# ATtiny85_Programmer.net
KiCad netlist of a schematic drawn in EAGLE
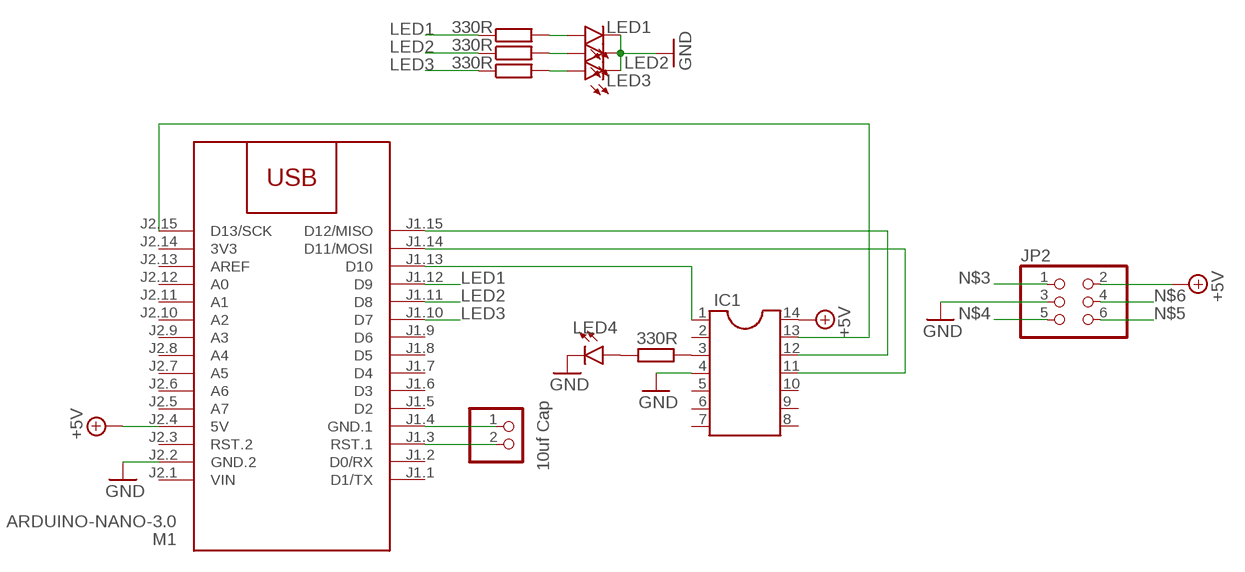
[diagram p0: schematic, sheet 1]

(export (version "E")
  (design (tool "Eeschema 10.0.6"))
  (components
    (comp (ref "IC1")
      (value "DIL14")
      (footprint "eagle-import:DIL14")
      (libsource (lib "eagle-import") (part "DIL14"))
    )
    (comp (ref "JP1")
      (value "10uf Cap")
      (footprint "eagle-import:1X02")
      (libsource (lib "eagle-import") (part "PINHD-1X2"))
    )
    (comp (ref "JP2")
      (value "PINHD-2X3")
      (footprint "eagle-import:2X03")
      (libsource (lib "eagle-import") (part "PINHD-2X3"))
    )
    (comp (ref "LED1")
      (value "LED3MM")
      (footprint "eagle-import:LED3MM")
      (libsource (lib "eagle-import") (part "LED3MM"))
    )
    (comp (ref "LED2")
      (value "LED3MM")
      (footprint "eagle-import:LED3MM")
      (libsource (lib "eagle-import") (part "LED3MM"))
    )
    (comp (ref "LED3")
      (value "LED3MM")
      (footprint "eagle-import:LED3MM")
      (libsource (lib "eagle-import") (part "LED3MM"))
    )
    (comp (ref "LED4")
      (value "LED3MM")
      (footprint "eagle-import:LED3MM")
      (libsource (lib "eagle-import") (part "LED3MM"))
    )
    (comp (ref "M1")
      (value "ARDUINO-NANO-3.0")
      (footprint "eagle-import:ARDUINO-NANO-3.0")
      (libsource (lib "eagle-import") (part "ARDUINO-NANO-3.0"))
    )
    (comp (ref "R1")
      (value "330R")
      (footprint "eagle-import:0207_10")
      (libsource (lib "eagle-import") (part "R-EU_0207/10"))
    )
    (comp (ref "R2")
      (value "330R")
      (footprint "eagle-import:0207_10")
      (libsource (lib "eagle-import") (part "R-EU_0207/10"))
    )
    (comp (ref "R3")
      (value "330R")
      (footprint "eagle-import:0207_10")
      (libsource (lib "eagle-import") (part "R-EU_0207/10"))
    )
    (comp (ref "R4")
      (value "330R")
      (footprint "eagle-import:0207_10")
      (libsource (lib "eagle-import") (part "R-EU_0207/10"))
    )
  )
  (nets
    (net (code "1") (name "+5V") (class "Default")
      (node (ref "IC1") (pin "14") (pinfunction "14_14") (pintype "passive"))
      (node (ref "JP2") (pin "2") (pinfunction "2_2") (pintype "passive"))
      (node (ref "M1") (pin "J2.4") (pinfunction "5V_J2.4") (pintype "power_in"))
    )
    (net (code "2") (name "/3V3") (class "Default")
      (node (ref "M1") (pin "J2.14") (pinfunction "3V3_J2.14") (pintype "power_in"))
    )
    (net (code "3") (name "/LED1") (class "Default")
      (node (ref "M1") (pin "J1.12") (pinfunction "D9_J1.12") (pintype "bidirectional"))
      (node (ref "R4") (pin "1") (pinfunction "1_1") (pintype "passive"))
    )
    (net (code "4") (name "/LED2") (class "Default")
      (node (ref "M1") (pin "J1.11") (pinfunction "D8_J1.11") (pintype "bidirectional"))
      (node (ref "R1") (pin "1") (pinfunction "1_1") (pintype "passive"))
    )
    (net (code "5") (name "/LED3") (class "Default")
      (node (ref "M1") (pin "J1.10") (pinfunction "D7_J1.10") (pintype "bidirectional"))
      (node (ref "R2") (pin "1") (pinfunction "1_1") (pintype "passive"))
    )
    (net (code "6") (name "/N$3") (class "Default")
      (node (ref "IC1") (pin "1") (pinfunction "1_1") (pintype "passive"))
      (node (ref "JP2") (pin "1") (pinfunction "1_1") (pintype "passive"))
      (node (ref "M1") (pin "J1.13") (pinfunction "D10_J1.13") (pintype "bidirectional"))
    )
    (net (code "7") (name "/N$4") (class "Default")
      (node (ref "IC1") (pin "11") (pinfunction "11_11") (pintype "passive"))
      (node (ref "JP2") (pin "5") (pinfunction "5_5") (pintype "passive"))
      (node (ref "M1") (pin "J1.14") (pinfunction "D11/MOSI_J1.14") (pintype "bidirectional"))
    )
    (net (code "8") (name "/N$5") (class "Default")
      (node (ref "IC1") (pin "12") (pinfunction "12_12") (pintype "passive"))
      (node (ref "JP2") (pin "6") (pinfunction "6_6") (pintype "passive"))
      (node (ref "M1") (pin "J1.15") (pinfunction "D12/MISO_J1.15") (pintype "bidirectional"))
    )
    (net (code "9") (name "/N$6") (class "Default")
      (node (ref "IC1") (pin "13") (pinfunction "13_13") (pintype "passive"))
      (node (ref "JP2") (pin "4") (pinfunction "4_4") (pintype "passive"))
      (node (ref "M1") (pin "J2.15") (pinfunction "D13/SCK_J2.15") (pintype "bidirectional"))
    )
    (net (code "10") (name "/VIN") (class "Default")
      (node (ref "M1") (pin "J2.1") (pinfunction "VIN_J2.1") (pintype "power_in"))
    )
    (net (code "11") (name "GND") (class "Default")
      (node (ref "IC1") (pin "4") (pinfunction "4_4") (pintype "passive"))
      (node (ref "JP2") (pin "3") (pinfunction "3_3") (pintype "passive"))
      (node (ref "LED1") (pin "K") (pinfunction "C_K") (pintype "passive"))
      (node (ref "LED2") (pin "K") (pinfunction "C_K") (pintype "passive"))
      (node (ref "LED3") (pin "K") (pinfunction "C_K") (pintype "passive"))
      (node (ref "LED4") (pin "K") (pinfunction "C_K") (pintype "passive"))
      (node (ref "M1") (pin "J2.2") (pinfunction "GND.2_J2.2") (pintype "power_in"))
    )
    (net (code "12") (name "Net-(IC1-Pad3)") (class "Default")
      (node (ref "IC1") (pin "3") (pinfunction "3_3") (pintype "passive"))
      (node (ref "R3") (pin "2") (pinfunction "2_2") (pintype "passive"))
    )
    (net (code "13") (name "Net-(LED1-PadA)") (class "Default")
      (node (ref "LED1") (pin "A") (pinfunction "A_A") (pintype "passive"))
      (node (ref "R4") (pin "2") (pinfunction "2_2") (pintype "passive"))
    )
    (net (code "14") (name "Net-(LED2-PadA)") (class "Default")
      (node (ref "LED2") (pin "A") (pinfunction "A_A") (pintype "passive"))
      (node (ref "R1") (pin "2") (pinfunction "2_2") (pintype "passive"))
    )
    (net (code "15") (name "Net-(LED3-PadA)") (class "Default")
      (node (ref "LED3") (pin "A") (pinfunction "A_A") (pintype "passive"))
      (node (ref "R2") (pin "2") (pinfunction "2_2") (pintype "passive"))
    )
    (net (code "16") (name "Net-(LED4-PadA)") (class "Default")
      (node (ref "LED4") (pin "A") (pinfunction "A_A") (pintype "passive"))
      (node (ref "R3") (pin "1") (pinfunction "1_1") (pintype "passive"))
    )
    (net (code "17") (name "Net-(M1-GND.1)") (class "Default")
      (node (ref "JP1") (pin "1") (pinfunction "1_1") (pintype "passive"))
      (node (ref "M1") (pin "J1.4") (pinfunction "GND.1_J1.4") (pintype "power_in"))
    )
    (net (code "18") (name "Net-(M1-RST.1)") (class "Default")
      (node (ref "JP1") (pin "2") (pinfunction "2_2") (pintype "passive"))
      (node (ref "M1") (pin "J1.3") (pinfunction "RST.1_J1.3") (pintype "bidirectional"))
    )
    (net (code "19") (name "unconnected-(IC1-Pad2)") (class "Default")
      (node (ref "IC1") (pin "2") (pinfunction "2_2") (pintype "passive"))
    )
    (net (code "20") (name "unconnected-(IC1-Pad5)") (class "Default")
      (node (ref "IC1") (pin "5") (pinfunction "5_5") (pintype "passive"))
    )
    (net (code "21") (name "unconnected-(IC1-Pad6)") (class "Default")
      (node (ref "IC1") (pin "6") (pinfunction "6_6") (pintype "passive"))
    )
    (net (code "22") (name "unconnected-(IC1-Pad7)") (class "Default")
      (node (ref "IC1") (pin "7") (pinfunction "7_7") (pintype "passive"))
    )
    (net (code "23") (name "unconnected-(IC1-Pad8)") (class "Default")
      (node (ref "IC1") (pin "8") (pinfunction "8_8") (pintype "passive"))
    )
    (net (code "24") (name "unconnected-(IC1-Pad9)") (class "Default")
      (node (ref "IC1") (pin "9") (pinfunction "9_9") (pintype "passive"))
    )
    (net (code "25") (name "unconnected-(IC1-Pad10)") (class "Default")
      (node (ref "IC1") (pin "10") (pinfunction "10_10") (pintype "passive"))
    )
    (net (code "26") (name "unconnected-(M1-A0-PadJ2.12)") (class "Default")
      (node (ref "M1") (pin "J2.12") (pinfunction "A0_J2.12") (pintype "bidirectional"))
    )
    (net (code "27") (name "unconnected-(M1-A1-PadJ2.11)") (class "Default")
      (node (ref "M1") (pin "J2.11") (pinfunction "A1_J2.11") (pintype "bidirectional"))
    )
    (net (code "28") (name "unconnected-(M1-A2-PadJ2.10)") (class "Default")
      (node (ref "M1") (pin "J2.10") (pinfunction "A2_J2.10") (pintype "bidirectional"))
    )
    (net (code "29") (name "unconnected-(M1-A3-PadJ2.9)") (class "Default")
      (node (ref "M1") (pin "J2.9") (pinfunction "A3_J2.9") (pintype "bidirectional"))
    )
    (net (code "30") (name "unconnected-(M1-A4-PadJ2.8)") (class "Default")
      (node (ref "M1") (pin "J2.8") (pinfunction "A4_J2.8") (pintype "bidirectional"))
    )
    (net (code "31") (name "unconnected-(M1-A5-PadJ2.7)") (class "Default")
      (node (ref "M1") (pin "J2.7") (pinfunction "A5_J2.7") (pintype "bidirectional"))
    )
    (net (code "32") (name "unconnected-(M1-A6-PadJ2.6)") (class "Default")
      (node (ref "M1") (pin "J2.6") (pinfunction "A6_J2.6") (pintype "bidirectional"))
    )
    (net (code "33") (name "unconnected-(M1-A7-PadJ2.5)") (class "Default")
      (node (ref "M1") (pin "J2.5") (pinfunction "A7_J2.5") (pintype "bidirectional"))
    )
    (net (code "34") (name "unconnected-(M1-AREF-PadJ2.13)") (class "Default")
      (node (ref "M1") (pin "J2.13") (pinfunction "AREF_J2.13") (pintype "bidirectional"))
    )
    (net (code "35") (name "unconnected-(M1-D0{slash}RX-PadJ1.2)") (class "Default")
      (node (ref "M1") (pin "J1.2") (pinfunction "D0/RX_J1.2") (pintype "bidirectional"))
    )
    (net (code "36") (name "unconnected-(M1-D1{slash}TX-PadJ1.1)") (class "Default")
      (node (ref "M1") (pin "J1.1") (pinfunction "D1/TX_J1.1") (pintype "bidirectional"))
    )
    (net (code "37") (name "unconnected-(M1-D2-PadJ1.5)") (class "Default")
      (node (ref "M1") (pin "J1.5") (pinfunction "D2_J1.5") (pintype "bidirectional"))
    )
    (net (code "38") (name "unconnected-(M1-D3-PadJ1.6)") (class "Default")
      (node (ref "M1") (pin "J1.6") (pinfunction "D3_J1.6") (pintype "bidirectional"))
    )
    (net (code "39") (name "unconnected-(M1-D4-PadJ1.7)") (class "Default")
      (node (ref "M1") (pin "J1.7") (pinfunction "D4_J1.7") (pintype "bidirectional"))
    )
    (net (code "40") (name "unconnected-(M1-D5-PadJ1.8)") (class "Default")
      (node (ref "M1") (pin "J1.8") (pinfunction "D5_J1.8") (pintype "bidirectional"))
    )
    (net (code "41") (name "unconnected-(M1-D6-PadJ1.9)") (class "Default")
      (node (ref "M1") (pin "J1.9") (pinfunction "D6_J1.9") (pintype "bidirectional"))
    )
    (net (code "42") (name "unconnected-(M1-RST.2-PadJ2.3)") (class "Default")
      (node (ref "M1") (pin "J2.3") (pinfunction "RST.2_J2.3") (pintype "bidirectional"))
    )
  )
)
